# ADS8686S_BLOCK_A.net
KiCad netlist of a schematic drawn in Altium Designer
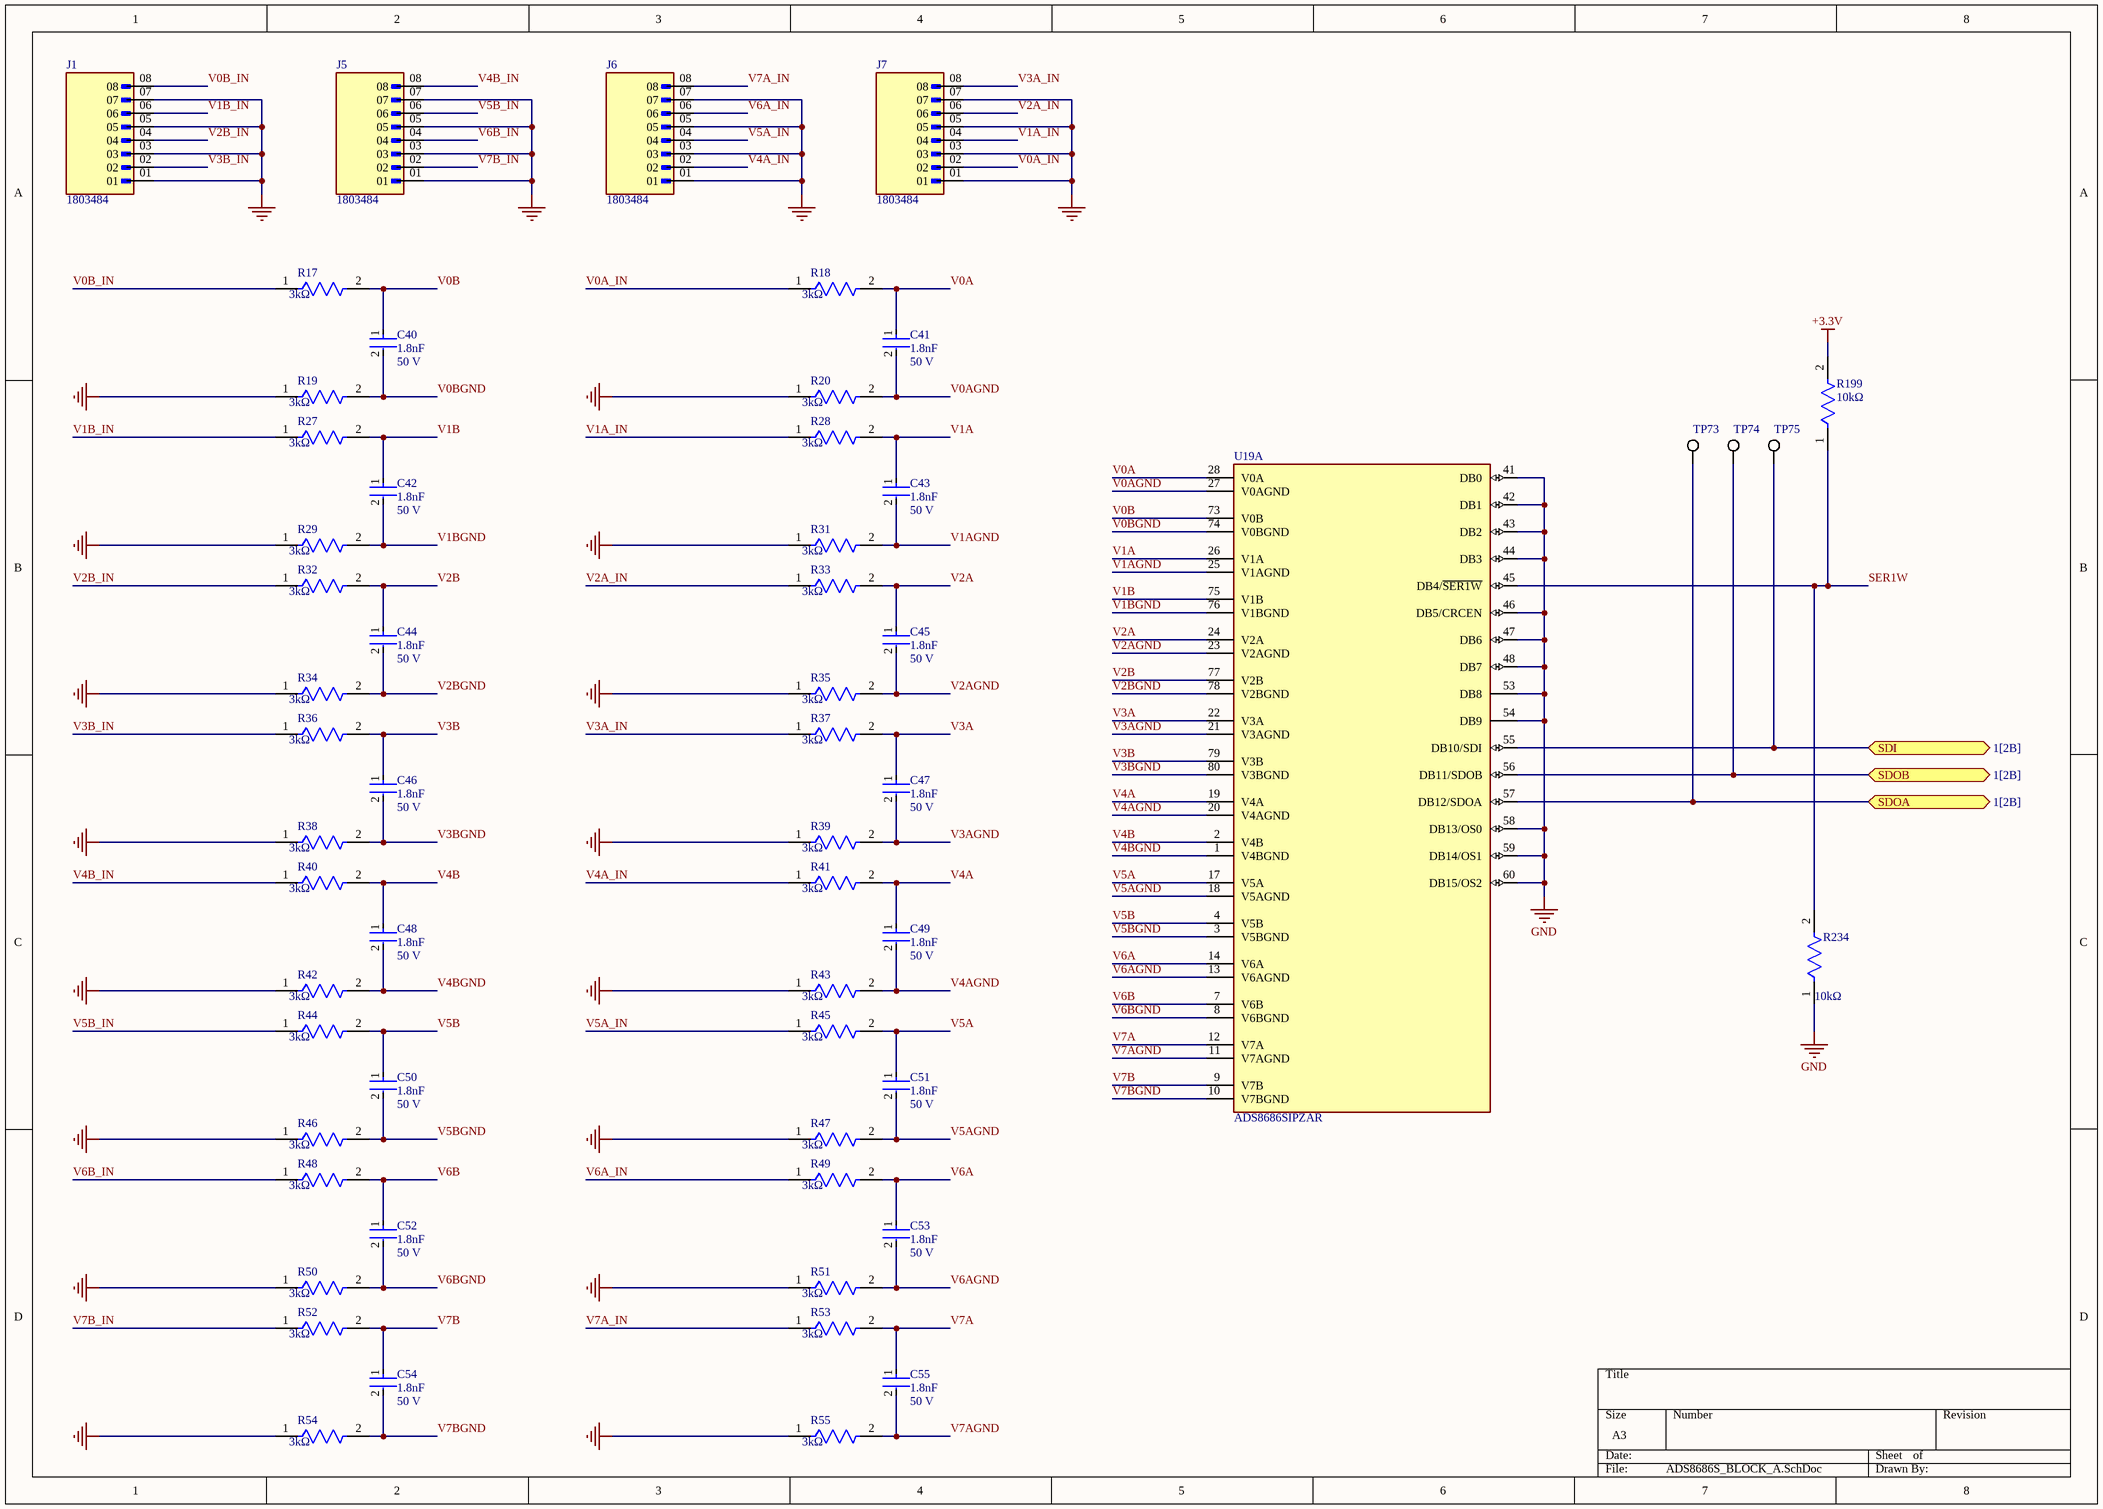
[diagram p0: ADS8686S_BLOCK_A.SchDoc]

(export (version "E")
  (design (tool "Eeschema 10.0.6"))
  (components
    (comp (ref "C40")
      (value "C0603C182J5GACTU")
      (footprint "FP-C0603C-CF-IPC_B")
      (description "CAP CER 1800PF 50V NP0 0603")
      (fields
        (field (name "OCTOPART") "https://octopart.com/c0603c182j5gactu-kemet-13174208")
        (field (name "TOLERANCE") "0.05")
        (field (name "CAPACITANCE") "1.8nF")
        (field (name "VOLTAGE RATING") "50 V")
      )
      (libsource (lib "Altium Content Vault") (part "b4654b650e69147ec39a6b967a45e02"))
    )
    (comp (ref "C41")
      (value "C0603C182J5GACTU")
      (footprint "FP-C0603C-CF-IPC_B")
      (description "CAP CER 1800PF 50V NP0 0603")
      (fields
        (field (name "OCTOPART") "https://octopart.com/c0603c182j5gactu-kemet-13174208")
        (field (name "TOLERANCE") "0.05")
        (field (name "CAPACITANCE") "1.8nF")
        (field (name "VOLTAGE RATING") "50 V")
      )
      (libsource (lib "Altium Content Vault") (part "b4654b650e69147ec39a6b967a45e02"))
    )
    (comp (ref "C42")
      (value "C0603C182J5GACTU")
      (footprint "FP-C0603C-CF-IPC_B")
      (description "CAP CER 1800PF 50V NP0 0603")
      (fields
        (field (name "OCTOPART") "https://octopart.com/c0603c182j5gactu-kemet-13174208")
        (field (name "TOLERANCE") "0.05")
        (field (name "CAPACITANCE") "1.8nF")
        (field (name "VOLTAGE RATING") "50 V")
      )
      (libsource (lib "Altium Content Vault") (part "b4654b650e69147ec39a6b967a45e02"))
    )
    (comp (ref "C43")
      (value "C0603C182J5GACTU")
      (footprint "FP-C0603C-CF-IPC_B")
      (description "CAP CER 1800PF 50V NP0 0603")
      (fields
        (field (name "OCTOPART") "https://octopart.com/c0603c182j5gactu-kemet-13174208")
        (field (name "TOLERANCE") "0.05")
        (field (name "CAPACITANCE") "1.8nF")
        (field (name "VOLTAGE RATING") "50 V")
      )
      (libsource (lib "Altium Content Vault") (part "b4654b650e69147ec39a6b967a45e02"))
    )
    (comp (ref "C44")
      (value "C0603C182J5GACTU")
      (footprint "FP-C0603C-CF-IPC_B")
      (description "CAP CER 1800PF 50V NP0 0603")
      (fields
        (field (name "OCTOPART") "https://octopart.com/c0603c182j5gactu-kemet-13174208")
        (field (name "TOLERANCE") "0.05")
        (field (name "CAPACITANCE") "1.8nF")
        (field (name "VOLTAGE RATING") "50 V")
      )
      (libsource (lib "Altium Content Vault") (part "b4654b650e69147ec39a6b967a45e02"))
    )
    (comp (ref "C45")
      (value "C0603C182J5GACTU")
      (footprint "FP-C0603C-CF-IPC_B")
      (description "CAP CER 1800PF 50V NP0 0603")
      (fields
        (field (name "OCTOPART") "https://octopart.com/c0603c182j5gactu-kemet-13174208")
        (field (name "TOLERANCE") "0.05")
        (field (name "CAPACITANCE") "1.8nF")
        (field (name "VOLTAGE RATING") "50 V")
      )
      (libsource (lib "Altium Content Vault") (part "b4654b650e69147ec39a6b967a45e02"))
    )
    (comp (ref "C46")
      (value "C0603C182J5GACTU")
      (footprint "FP-C0603C-CF-IPC_B")
      (description "CAP CER 1800PF 50V NP0 0603")
      (fields
        (field (name "OCTOPART") "https://octopart.com/c0603c182j5gactu-kemet-13174208")
        (field (name "TOLERANCE") "0.05")
        (field (name "CAPACITANCE") "1.8nF")
        (field (name "VOLTAGE RATING") "50 V")
      )
      (libsource (lib "Altium Content Vault") (part "b4654b650e69147ec39a6b967a45e02"))
    )
    (comp (ref "C47")
      (value "C0603C182J5GACTU")
      (footprint "FP-C0603C-CF-IPC_B")
      (description "CAP CER 1800PF 50V NP0 0603")
      (fields
        (field (name "OCTOPART") "https://octopart.com/c0603c182j5gactu-kemet-13174208")
        (field (name "TOLERANCE") "0.05")
        (field (name "CAPACITANCE") "1.8nF")
        (field (name "VOLTAGE RATING") "50 V")
      )
      (libsource (lib "Altium Content Vault") (part "b4654b650e69147ec39a6b967a45e02"))
    )
    (comp (ref "C48")
      (value "C0603C182J5GACTU")
      (footprint "FP-C0603C-CF-IPC_B")
      (description "CAP CER 1800PF 50V NP0 0603")
      (fields
        (field (name "OCTOPART") "https://octopart.com/c0603c182j5gactu-kemet-13174208")
        (field (name "TOLERANCE") "0.05")
        (field (name "CAPACITANCE") "1.8nF")
        (field (name "VOLTAGE RATING") "50 V")
      )
      (libsource (lib "Altium Content Vault") (part "b4654b650e69147ec39a6b967a45e02"))
    )
    (comp (ref "C49")
      (value "C0603C182J5GACTU")
      (footprint "FP-C0603C-CF-IPC_B")
      (description "CAP CER 1800PF 50V NP0 0603")
      (fields
        (field (name "OCTOPART") "https://octopart.com/c0603c182j5gactu-kemet-13174208")
        (field (name "TOLERANCE") "0.05")
        (field (name "CAPACITANCE") "1.8nF")
        (field (name "VOLTAGE RATING") "50 V")
      )
      (libsource (lib "Altium Content Vault") (part "b4654b650e69147ec39a6b967a45e02"))
    )
    (comp (ref "C50")
      (value "C0603C182J5GACTU")
      (footprint "FP-C0603C-CF-IPC_B")
      (description "CAP CER 1800PF 50V NP0 0603")
      (fields
        (field (name "OCTOPART") "https://octopart.com/c0603c182j5gactu-kemet-13174208")
        (field (name "TOLERANCE") "0.05")
        (field (name "CAPACITANCE") "1.8nF")
        (field (name "VOLTAGE RATING") "50 V")
      )
      (libsource (lib "Altium Content Vault") (part "b4654b650e69147ec39a6b967a45e02"))
    )
    (comp (ref "C51")
      (value "C0603C182J5GACTU")
      (footprint "FP-C0603C-CF-IPC_B")
      (description "CAP CER 1800PF 50V NP0 0603")
      (fields
        (field (name "OCTOPART") "https://octopart.com/c0603c182j5gactu-kemet-13174208")
        (field (name "TOLERANCE") "0.05")
        (field (name "CAPACITANCE") "1.8nF")
        (field (name "VOLTAGE RATING") "50 V")
      )
      (libsource (lib "Altium Content Vault") (part "b4654b650e69147ec39a6b967a45e02"))
    )
    (comp (ref "C52")
      (value "C0603C182J5GACTU")
      (footprint "FP-C0603C-CF-IPC_B")
      (description "CAP CER 1800PF 50V NP0 0603")
      (fields
        (field (name "OCTOPART") "https://octopart.com/c0603c182j5gactu-kemet-13174208")
        (field (name "TOLERANCE") "0.05")
        (field (name "CAPACITANCE") "1.8nF")
        (field (name "VOLTAGE RATING") "50 V")
      )
      (libsource (lib "Altium Content Vault") (part "b4654b650e69147ec39a6b967a45e02"))
    )
    (comp (ref "C53")
      (value "C0603C182J5GACTU")
      (footprint "FP-C0603C-CF-IPC_B")
      (description "CAP CER 1800PF 50V NP0 0603")
      (fields
        (field (name "OCTOPART") "https://octopart.com/c0603c182j5gactu-kemet-13174208")
        (field (name "TOLERANCE") "0.05")
        (field (name "CAPACITANCE") "1.8nF")
        (field (name "VOLTAGE RATING") "50 V")
      )
      (libsource (lib "Altium Content Vault") (part "b4654b650e69147ec39a6b967a45e02"))
    )
    (comp (ref "C54")
      (value "C0603C182J5GACTU")
      (footprint "FP-C0603C-CF-IPC_B")
      (description "CAP CER 1800PF 50V NP0 0603")
      (fields
        (field (name "OCTOPART") "https://octopart.com/c0603c182j5gactu-kemet-13174208")
        (field (name "TOLERANCE") "0.05")
        (field (name "CAPACITANCE") "1.8nF")
        (field (name "VOLTAGE RATING") "50 V")
      )
      (libsource (lib "Altium Content Vault") (part "b4654b650e69147ec39a6b967a45e02"))
    )
    (comp (ref "C55")
      (value "C0603C182J5GACTU")
      (footprint "FP-C0603C-CF-IPC_B")
      (description "CAP CER 1800PF 50V NP0 0603")
      (fields
        (field (name "OCTOPART") "https://octopart.com/c0603c182j5gactu-kemet-13174208")
        (field (name "TOLERANCE") "0.05")
        (field (name "CAPACITANCE") "1.8nF")
        (field (name "VOLTAGE RATING") "50 V")
      )
      (libsource (lib "Altium Content Vault") (part "b4654b650e69147ec39a6b967a45e02"))
    )
    (comp (ref "J1")
      (value "1803484")
      (footprint "1803484:PHOENIX_1803484")
      (fields (field (name "MF") "{'manufacturer': u'Phoenix Contact'}"))
      (libsource (lib "*") (part "1803484"))
    )
    (comp (ref "J5")
      (value "1803484")
      (footprint "1803484:PHOENIX_1803484")
      (fields (field (name "MF") "{'manufacturer': u'Phoenix Contact'}"))
      (libsource (lib "*") (part "1803484"))
    )
    (comp (ref "J6")
      (value "1803484")
      (footprint "1803484:PHOENIX_1803484")
      (fields (field (name "MF") "{'manufacturer': u'Phoenix Contact'}"))
      (libsource (lib "*") (part "1803484"))
    )
    (comp (ref "J7")
      (value "1803484")
      (footprint "1803484:PHOENIX_1803484")
      (fields (field (name "MF") "{'manufacturer': u'Phoenix Contact'}"))
      (libsource (lib "*") (part "1803484"))
    )
    (comp (ref "R17")
      (value "AC0603FR-073KL")
      (footprint "FP-AC0603-IPC_B")
      (description "RES 3kΩ 1.00% 0.1W 0603")
      (fields (field (name "TOLERANCE") "1%") (field (name "RESISTANCE") "3kΩ"))
      (libsource (lib "Altium Content Vault") (part "1029c3af85768c4190bb7ad29bc67b5"))
    )
    (comp (ref "R18")
      (value "AC0603FR-073KL")
      (footprint "FP-AC0603-IPC_B")
      (description "RES 3kΩ 1.00% 0.1W 0603")
      (fields (field (name "TOLERANCE") "1%") (field (name "RESISTANCE") "3kΩ"))
      (libsource (lib "Altium Content Vault") (part "1029c3af85768c4190bb7ad29bc67b5"))
    )
    (comp (ref "R19")
      (value "AC0603FR-073KL")
      (footprint "FP-AC0603-IPC_B")
      (description "RES 3kΩ 1.00% 0.1W 0603")
      (fields (field (name "TOLERANCE") "1%") (field (name "RESISTANCE") "3kΩ"))
      (libsource (lib "Altium Content Vault") (part "1029c3af85768c4190bb7ad29bc67b5"))
    )
    (comp (ref "R20")
      (value "AC0603FR-073KL")
      (footprint "FP-AC0603-IPC_B")
      (description "RES 3kΩ 1.00% 0.1W 0603")
      (fields (field (name "TOLERANCE") "1%") (field (name "RESISTANCE") "3kΩ"))
      (libsource (lib "Altium Content Vault") (part "1029c3af85768c4190bb7ad29bc67b5"))
    )
    (comp (ref "R27")
      (value "AC0603FR-073KL")
      (footprint "FP-AC0603-IPC_B")
      (description "RES 3kΩ 1.00% 0.1W 0603")
      (fields (field (name "TOLERANCE") "1%") (field (name "RESISTANCE") "3kΩ"))
      (libsource (lib "Altium Content Vault") (part "1029c3af85768c4190bb7ad29bc67b5"))
    )
    (comp (ref "R28")
      (value "AC0603FR-073KL")
      (footprint "FP-AC0603-IPC_B")
      (description "RES 3kΩ 1.00% 0.1W 0603")
      (fields (field (name "TOLERANCE") "1%") (field (name "RESISTANCE") "3kΩ"))
      (libsource (lib "Altium Content Vault") (part "1029c3af85768c4190bb7ad29bc67b5"))
    )
    (comp (ref "R29")
      (value "AC0603FR-073KL")
      (footprint "FP-AC0603-IPC_B")
      (description "RES 3kΩ 1.00% 0.1W 0603")
      (fields (field (name "TOLERANCE") "1%") (field (name "RESISTANCE") "3kΩ"))
      (libsource (lib "Altium Content Vault") (part "1029c3af85768c4190bb7ad29bc67b5"))
    )
    (comp (ref "R31")
      (value "AC0603FR-073KL")
      (footprint "FP-AC0603-IPC_B")
      (description "RES 3kΩ 1.00% 0.1W 0603")
      (fields (field (name "TOLERANCE") "1%") (field (name "RESISTANCE") "3kΩ"))
      (libsource (lib "Altium Content Vault") (part "1029c3af85768c4190bb7ad29bc67b5"))
    )
    (comp (ref "R32")
      (value "AC0603FR-073KL")
      (footprint "FP-AC0603-IPC_B")
      (description "RES 3kΩ 1.00% 0.1W 0603")
      (fields (field (name "TOLERANCE") "1%") (field (name "RESISTANCE") "3kΩ"))
      (libsource (lib "Altium Content Vault") (part "1029c3af85768c4190bb7ad29bc67b5"))
    )
    (comp (ref "R33")
      (value "AC0603FR-073KL")
      (footprint "FP-AC0603-IPC_B")
      (description "RES 3kΩ 1.00% 0.1W 0603")
      (fields (field (name "TOLERANCE") "1%") (field (name "RESISTANCE") "3kΩ"))
      (libsource (lib "Altium Content Vault") (part "1029c3af85768c4190bb7ad29bc67b5"))
    )
    (comp (ref "R34")
      (value "AC0603FR-073KL")
      (footprint "FP-AC0603-IPC_B")
      (description "RES 3kΩ 1.00% 0.1W 0603")
      (fields (field (name "TOLERANCE") "1%") (field (name "RESISTANCE") "3kΩ"))
      (libsource (lib "Altium Content Vault") (part "1029c3af85768c4190bb7ad29bc67b5"))
    )
    (comp (ref "R35")
      (value "AC0603FR-073KL")
      (footprint "FP-AC0603-IPC_B")
      (description "RES 3kΩ 1.00% 0.1W 0603")
      (fields (field (name "TOLERANCE") "1%") (field (name "RESISTANCE") "3kΩ"))
      (libsource (lib "Altium Content Vault") (part "1029c3af85768c4190bb7ad29bc67b5"))
    )
    (comp (ref "R36")
      (value "AC0603FR-073KL")
      (footprint "FP-AC0603-IPC_B")
      (description "RES 3kΩ 1.00% 0.1W 0603")
      (fields (field (name "TOLERANCE") "1%") (field (name "RESISTANCE") "3kΩ"))
      (libsource (lib "Altium Content Vault") (part "1029c3af85768c4190bb7ad29bc67b5"))
    )
    (comp (ref "R37")
      (value "AC0603FR-073KL")
      (footprint "FP-AC0603-IPC_B")
      (description "RES 3kΩ 1.00% 0.1W 0603")
      (fields (field (name "TOLERANCE") "1%") (field (name "RESISTANCE") "3kΩ"))
      (libsource (lib "Altium Content Vault") (part "1029c3af85768c4190bb7ad29bc67b5"))
    )
    (comp (ref "R38")
      (value "AC0603FR-073KL")
      (footprint "FP-AC0603-IPC_B")
      (description "RES 3kΩ 1.00% 0.1W 0603")
      (fields (field (name "TOLERANCE") "1%") (field (name "RESISTANCE") "3kΩ"))
      (libsource (lib "Altium Content Vault") (part "1029c3af85768c4190bb7ad29bc67b5"))
    )
    (comp (ref "R39")
      (value "AC0603FR-073KL")
      (footprint "FP-AC0603-IPC_B")
      (description "RES 3kΩ 1.00% 0.1W 0603")
      (fields (field (name "TOLERANCE") "1%") (field (name "RESISTANCE") "3kΩ"))
      (libsource (lib "Altium Content Vault") (part "1029c3af85768c4190bb7ad29bc67b5"))
    )
    (comp (ref "R40")
      (value "AC0603FR-073KL")
      (footprint "FP-AC0603-IPC_B")
      (description "RES 3kΩ 1.00% 0.1W 0603")
      (fields (field (name "TOLERANCE") "1%") (field (name "RESISTANCE") "3kΩ"))
      (libsource (lib "Altium Content Vault") (part "1029c3af85768c4190bb7ad29bc67b5"))
    )
    (comp (ref "R41")
      (value "AC0603FR-073KL")
      (footprint "FP-AC0603-IPC_B")
      (description "RES 3kΩ 1.00% 0.1W 0603")
      (fields (field (name "TOLERANCE") "1%") (field (name "RESISTANCE") "3kΩ"))
      (libsource (lib "Altium Content Vault") (part "1029c3af85768c4190bb7ad29bc67b5"))
    )
    (comp (ref "R42")
      (value "AC0603FR-073KL")
      (footprint "FP-AC0603-IPC_B")
      (description "RES 3kΩ 1.00% 0.1W 0603")
      (fields (field (name "TOLERANCE") "1%") (field (name "RESISTANCE") "3kΩ"))
      (libsource (lib "Altium Content Vault") (part "1029c3af85768c4190bb7ad29bc67b5"))
    )
    (comp (ref "R43")
      (value "AC0603FR-073KL")
      (footprint "FP-AC0603-IPC_B")
      (description "RES 3kΩ 1.00% 0.1W 0603")
      (fields (field (name "TOLERANCE") "1%") (field (name "RESISTANCE") "3kΩ"))
      (libsource (lib "Altium Content Vault") (part "1029c3af85768c4190bb7ad29bc67b5"))
    )
    (comp (ref "R44")
      (value "AC0603FR-073KL")
      (footprint "FP-AC0603-IPC_B")
      (description "RES 3kΩ 1.00% 0.1W 0603")
      (fields (field (name "TOLERANCE") "1%") (field (name "RESISTANCE") "3kΩ"))
      (libsource (lib "Altium Content Vault") (part "1029c3af85768c4190bb7ad29bc67b5"))
    )
    (comp (ref "R45")
      (value "AC0603FR-073KL")
      (footprint "FP-AC0603-IPC_B")
      (description "RES 3kΩ 1.00% 0.1W 0603")
      (fields (field (name "TOLERANCE") "1%") (field (name "RESISTANCE") "3kΩ"))
      (libsource (lib "Altium Content Vault") (part "1029c3af85768c4190bb7ad29bc67b5"))
    )
    (comp (ref "R46")
      (value "AC0603FR-073KL")
      (footprint "FP-AC0603-IPC_B")
      (description "RES 3kΩ 1.00% 0.1W 0603")
      (fields (field (name "TOLERANCE") "1%") (field (name "RESISTANCE") "3kΩ"))
      (libsource (lib "Altium Content Vault") (part "1029c3af85768c4190bb7ad29bc67b5"))
    )
    (comp (ref "R47")
      (value "AC0603FR-073KL")
      (footprint "FP-AC0603-IPC_B")
      (description "RES 3kΩ 1.00% 0.1W 0603")
      (fields (field (name "TOLERANCE") "1%") (field (name "RESISTANCE") "3kΩ"))
      (libsource (lib "Altium Content Vault") (part "1029c3af85768c4190bb7ad29bc67b5"))
    )
    (comp (ref "R48")
      (value "AC0603FR-073KL")
      (footprint "FP-AC0603-IPC_B")
      (description "RES 3kΩ 1.00% 0.1W 0603")
      (fields (field (name "TOLERANCE") "1%") (field (name "RESISTANCE") "3kΩ"))
      (libsource (lib "Altium Content Vault") (part "1029c3af85768c4190bb7ad29bc67b5"))
    )
    (comp (ref "R49")
      (value "AC0603FR-073KL")
      (footprint "FP-AC0603-IPC_B")
      (description "RES 3kΩ 1.00% 0.1W 0603")
      (fields (field (name "TOLERANCE") "1%") (field (name "RESISTANCE") "3kΩ"))
      (libsource (lib "Altium Content Vault") (part "1029c3af85768c4190bb7ad29bc67b5"))
    )
    (comp (ref "R50")
      (value "AC0603FR-073KL")
      (footprint "FP-AC0603-IPC_B")
      (description "RES 3kΩ 1.00% 0.1W 0603")
      (fields (field (name "TOLERANCE") "1%") (field (name "RESISTANCE") "3kΩ"))
      (libsource (lib "Altium Content Vault") (part "1029c3af85768c4190bb7ad29bc67b5"))
    )
    (comp (ref "R51")
      (value "AC0603FR-073KL")
      (footprint "FP-AC0603-IPC_B")
      (description "RES 3kΩ 1.00% 0.1W 0603")
      (fields (field (name "TOLERANCE") "1%") (field (name "RESISTANCE") "3kΩ"))
      (libsource (lib "Altium Content Vault") (part "1029c3af85768c4190bb7ad29bc67b5"))
    )
    (comp (ref "R52")
      (value "AC0603FR-073KL")
      (footprint "FP-AC0603-IPC_B")
      (description "RES 3kΩ 1.00% 0.1W 0603")
      (fields (field (name "TOLERANCE") "1%") (field (name "RESISTANCE") "3kΩ"))
      (libsource (lib "Altium Content Vault") (part "1029c3af85768c4190bb7ad29bc67b5"))
    )
    (comp (ref "R53")
      (value "AC0603FR-073KL")
      (footprint "FP-AC0603-IPC_B")
      (description "RES 3kΩ 1.00% 0.1W 0603")
      (fields (field (name "TOLERANCE") "1%") (field (name "RESISTANCE") "3kΩ"))
      (libsource (lib "Altium Content Vault") (part "1029c3af85768c4190bb7ad29bc67b5"))
    )
    (comp (ref "R54")
      (value "AC0603FR-073KL")
      (footprint "FP-AC0603-IPC_B")
      (description "RES 3kΩ 1.00% 0.1W 0603")
      (fields (field (name "TOLERANCE") "1%") (field (name "RESISTANCE") "3kΩ"))
      (libsource (lib "Altium Content Vault") (part "1029c3af85768c4190bb7ad29bc67b5"))
    )
    (comp (ref "R55")
      (value "AC0603FR-073KL")
      (footprint "FP-AC0603-IPC_B")
      (description "RES 3kΩ 1.00% 0.1W 0603")
      (fields (field (name "TOLERANCE") "1%") (field (name "RESISTANCE") "3kΩ"))
      (libsource (lib "Altium Content Vault") (part "1029c3af85768c4190bb7ad29bc67b5"))
    )
    (comp (ref "R199")
      (value "RC0603FR-0710KL")
      (footprint "FP-RC0603-0_55-IPC_B")
      (description "RES 10K OHM 1% 1/10W 0603")
      (fields (field (name "TOLERANCE") "1%") (field (name "RESISTANCE") "10kΩ"))
      (libsource (lib "Altium Content Vault") (part "1029c3af85768c4190bb7ad29bc67b5"))
    )
    (comp (ref "R234")
      (value "RC0603FR-0710KL")
      (footprint "FP-RC0603-0_55-IPC_B")
      (description "RES 10K OHM 1% 1/10W 0603")
      (fields (field (name "TOLERANCE") "1%") (field (name "RESISTANCE") "10kΩ"))
      (libsource (lib "Altium Content Vault") (part "1029c3af85768c4190bb7ad29bc67b5"))
    )
    (comp (ref "TP73")
      (value "5019")
      (footprint "KSTN-5019_V")
      (description "Test Point, 1 Position SMD, RoHS, Tape and Reel")
      (libsource (lib "Altium Content Vault") (part "TESTPOINT_WHITE"))
    )
    (comp (ref "TP74")
      (value "5019")
      (footprint "KSTN-5019_V")
      (description "Test Point, 1 Position SMD, RoHS, Tape and Reel")
      (libsource (lib "Altium Content Vault") (part "TESTPOINT_WHITE"))
    )
    (comp (ref "TP75")
      (value "5019")
      (footprint "KSTN-5019_V")
      (description "Test Point, 1 Position SMD, RoHS, Tape and Reel")
      (libsource (lib "Altium Content Vault") (part "TESTPOINT_WHITE"))
    )
    (comp (ref "U19")
      (value "ADS8686SIPZAR")
      (footprint "TI-RECOMMENDED")
      (fields (field (name "MANUFACTURER") "Texas Instruments"))
      (libsource (lib "ADS8686S") (part "ADS8686SIPZAR"))
    )
  )
  (nets
    (net (code "1") (name "+3.3V") (class "Default")
      (node (ref "R199") (pin "2") (pinfunction "2_2") (pintype "passive"))
    )
    (net (code "2") (name "/SDI") (class "Default")
      (node (ref "TP75") (pin "1") (pinfunction "1_1") (pintype "passive"))
      (node (ref "U19") (pin "55") (pinfunction "DB10/SDI_55") (pintype "bidirectional"))
    )
    (net (code "3") (name "/SDOA") (class "Default")
      (node (ref "TP73") (pin "1") (pinfunction "1_1") (pintype "passive"))
      (node (ref "U19") (pin "57") (pinfunction "DB12/SDOA_57") (pintype "bidirectional"))
    )
    (net (code "4") (name "/SDOB") (class "Default")
      (node (ref "TP74") (pin "1") (pinfunction "1_1") (pintype "passive"))
      (node (ref "U19") (pin "56") (pinfunction "DB11/SDOB_56") (pintype "bidirectional"))
    )
    (net (code "5") (name "/SER1W") (class "Default")
      (node (ref "R199") (pin "1") (pinfunction "1_1") (pintype "passive"))
      (node (ref "R234") (pin "2") (pinfunction "2_2") (pintype "passive"))
      (node (ref "U19") (pin "45") (pinfunction "DB4/~{SER1W}_45") (pintype "bidirectional"))
    )
    (net (code "6") (name "/V0A") (class "Default")
      (node (ref "C41") (pin "1") (pinfunction "1_1") (pintype "passive"))
      (node (ref "R18") (pin "2") (pinfunction "2_2") (pintype "passive"))
      (node (ref "U19") (pin "28") (pinfunction "V0A_28") (pintype "power_in"))
    )
    (net (code "7") (name "/V0AGND") (class "Default")
      (node (ref "C41") (pin "2") (pinfunction "2_2") (pintype "passive"))
      (node (ref "R20") (pin "2") (pinfunction "2_2") (pintype "passive"))
      (node (ref "U19") (pin "27") (pinfunction "V0AGND_27") (pintype "power_in"))
    )
    (net (code "8") (name "/V0A_IN") (class "Default")
      (node (ref "J7") (pin "02") (pinfunction "02_02") (pintype "passive"))
      (node (ref "R18") (pin "1") (pinfunction "1_1") (pintype "passive"))
    )
    (net (code "9") (name "/V0B") (class "Default")
      (node (ref "C40") (pin "1") (pinfunction "1_1") (pintype "passive"))
      (node (ref "R17") (pin "2") (pinfunction "2_2") (pintype "passive"))
      (node (ref "U19") (pin "73") (pinfunction "V0B_73") (pintype "power_in"))
    )
    (net (code "10") (name "/V0BGND") (class "Default")
      (node (ref "C40") (pin "2") (pinfunction "2_2") (pintype "passive"))
      (node (ref "R19") (pin "2") (pinfunction "2_2") (pintype "passive"))
      (node (ref "U19") (pin "74") (pinfunction "V0BGND_74") (pintype "power_in"))
    )
    (net (code "11") (name "/V0B_IN") (class "Default")
      (node (ref "J1") (pin "08") (pinfunction "08_08") (pintype "passive"))
      (node (ref "R17") (pin "1") (pinfunction "1_1") (pintype "passive"))
    )
    (net (code "12") (name "/V1A") (class "Default")
      (node (ref "C43") (pin "1") (pinfunction "1_1") (pintype "passive"))
      (node (ref "R28") (pin "2") (pinfunction "2_2") (pintype "passive"))
      (node (ref "U19") (pin "26") (pinfunction "V1A_26") (pintype "power_in"))
    )
    (net (code "13") (name "/V1AGND") (class "Default")
      (node (ref "C43") (pin "2") (pinfunction "2_2") (pintype "passive"))
      (node (ref "R31") (pin "2") (pinfunction "2_2") (pintype "passive"))
      (node (ref "U19") (pin "25") (pinfunction "V1AGND_25") (pintype "power_in"))
    )
    (net (code "14") (name "/V1A_IN") (class "Default")
      (node (ref "J7") (pin "04") (pinfunction "04_04") (pintype "passive"))
      (node (ref "R28") (pin "1") (pinfunction "1_1") (pintype "passive"))
    )
    (net (code "15") (name "/V1B") (class "Default")
      (node (ref "C42") (pin "1") (pinfunction "1_1") (pintype "passive"))
      (node (ref "R27") (pin "2") (pinfunction "2_2") (pintype "passive"))
      (node (ref "U19") (pin "75") (pinfunction "V1B_75") (pintype "power_in"))
    )
    (net (code "16") (name "/V1BGND") (class "Default")
      (node (ref "C42") (pin "2") (pinfunction "2_2") (pintype "passive"))
      (node (ref "R29") (pin "2") (pinfunction "2_2") (pintype "passive"))
      (node (ref "U19") (pin "76") (pinfunction "V1BGND_76") (pintype "power_in"))
    )
    (net (code "17") (name "/V1B_IN") (class "Default")
      (node (ref "J1") (pin "06") (pinfunction "06_06") (pintype "passive"))
      (node (ref "R27") (pin "1") (pinfunction "1_1") (pintype "passive"))
    )
    (net (code "18") (name "/V2A") (class "Default")
      (node (ref "C45") (pin "1") (pinfunction "1_1") (pintype "passive"))
      (node (ref "R33") (pin "2") (pinfunction "2_2") (pintype "passive"))
      (node (ref "U19") (pin "24") (pinfunction "V2A_24") (pintype "power_in"))
    )
    (net (code "19") (name "/V2AGND") (class "Default")
      (node (ref "C45") (pin "2") (pinfunction "2_2") (pintype "passive"))
      (node (ref "R35") (pin "2") (pinfunction "2_2") (pintype "passive"))
      (node (ref "U19") (pin "23") (pinfunction "V2AGND_23") (pintype "power_in"))
    )
    (net (code "20") (name "/V2A_IN") (class "Default")
      (node (ref "J7") (pin "06") (pinfunction "06_06") (pintype "passive"))
      (node (ref "R33") (pin "1") (pinfunction "1_1") (pintype "passive"))
    )
    (net (code "21") (name "/V2B") (class "Default")
      (node (ref "C44") (pin "1") (pinfunction "1_1") (pintype "passive"))
      (node (ref "R32") (pin "2") (pinfunction "2_2") (pintype "passive"))
      (node (ref "U19") (pin "77") (pinfunction "V2B_77") (pintype "power_in"))
    )
    (net (code "22") (name "/V2BGND") (class "Default")
      (node (ref "C44") (pin "2") (pinfunction "2_2") (pintype "passive"))
      (node (ref "R34") (pin "2") (pinfunction "2_2") (pintype "passive"))
      (node (ref "U19") (pin "78") (pinfunction "V2BGND_78") (pintype "power_in"))
    )
    (net (code "23") (name "/V2B_IN") (class "Default")
      (node (ref "J1") (pin "04") (pinfunction "04_04") (pintype "passive"))
      (node (ref "R32") (pin "1") (pinfunction "1_1") (pintype "passive"))
    )
    (net (code "24") (name "/V3A") (class "Default")
      (node (ref "C47") (pin "1") (pinfunction "1_1") (pintype "passive"))
      (node (ref "R37") (pin "2") (pinfunction "2_2") (pintype "passive"))
      (node (ref "U19") (pin "22") (pinfunction "V3A_22") (pintype "power_in"))
    )
    (net (code "25") (name "/V3AGND") (class "Default")
      (node (ref "C47") (pin "2") (pinfunction "2_2") (pintype "passive"))
      (node (ref "R39") (pin "2") (pinfunction "2_2") (pintype "passive"))
      (node (ref "U19") (pin "21") (pinfunction "V3AGND_21") (pintype "power_in"))
    )
    (net (code "26") (name "/V3A_IN") (class "Default")
      (node (ref "J7") (pin "08") (pinfunction "08_08") (pintype "passive"))
      (node (ref "R37") (pin "1") (pinfunction "1_1") (pintype "passive"))
    )
    (net (code "27") (name "/V3B") (class "Default")
      (node (ref "C46") (pin "1") (pinfunction "1_1") (pintype "passive"))
      (node (ref "R36") (pin "2") (pinfunction "2_2") (pintype "passive"))
      (node (ref "U19") (pin "79") (pinfunction "V3B_79") (pintype "power_in"))
    )
    (net (code "28") (name "/V3BGND") (class "Default")
      (node (ref "C46") (pin "2") (pinfunction "2_2") (pintype "passive"))
      (node (ref "R38") (pin "2") (pinfunction "2_2") (pintype "passive"))
      (node (ref "U19") (pin "80") (pinfunction "V3BGND_80") (pintype "power_in"))
    )
    (net (code "29") (name "/V3B_IN") (class "Default")
      (node (ref "J1") (pin "02") (pinfunction "02_02") (pintype "passive"))
      (node (ref "R36") (pin "1") (pinfunction "1_1") (pintype "passive"))
    )
    (net (code "30") (name "/V4A") (class "Default")
      (node (ref "C49") (pin "1") (pinfunction "1_1") (pintype "passive"))
      (node (ref "R41") (pin "2") (pinfunction "2_2") (pintype "passive"))
      (node (ref "U19") (pin "19") (pinfunction "V4A_19") (pintype "power_in"))
    )
    (net (code "31") (name "/V4AGND") (class "Default")
      (node (ref "C49") (pin "2") (pinfunction "2_2") (pintype "passive"))
      (node (ref "R43") (pin "2") (pinfunction "2_2") (pintype "passive"))
      (node (ref "U19") (pin "20") (pinfunction "V4AGND_20") (pintype "power_in"))
    )
    (net (code "32") (name "/V4A_IN") (class "Default")
      (node (ref "J6") (pin "02") (pinfunction "02_02") (pintype "passive"))
      (node (ref "R41") (pin "1") (pinfunction "1_1") (pintype "passive"))
    )
    (net (code "33") (name "/V4B") (class "Default")
      (node (ref "C48") (pin "1") (pinfunction "1_1") (pintype "passive"))
      (node (ref "R40") (pin "2") (pinfunction "2_2") (pintype "passive"))
      (node (ref "U19") (pin "2") (pinfunction "V4B_2") (pintype "power_in"))
    )
    (net (code "34") (name "/V4BGND") (class "Default")
      (node (ref "C48") (pin "2") (pinfunction "2_2") (pintype "passive"))
      (node (ref "R42") (pin "2") (pinfunction "2_2") (pintype "passive"))
      (node (ref "U19") (pin "1") (pinfunction "V4BGND_1") (pintype "power_in"))
    )
    (net (code "35") (name "/V4B_IN") (class "Default")
      (node (ref "J5") (pin "08") (pinfunction "08_08") (pintype "passive"))
      (node (ref "R40") (pin "1") (pinfunction "1_1") (pintype "passive"))
    )
    (net (code "36") (name "/V5A") (class "Default")
      (node (ref "C51") (pin "1") (pinfunction "1_1") (pintype "passive"))
      (node (ref "R45") (pin "2") (pinfunction "2_2") (pintype "passive"))
      (node (ref "U19") (pin "17") (pinfunction "V5A_17") (pintype "power_in"))
    )
    (net (code "37") (name "/V5AGND") (class "Default")
      (node (ref "C51") (pin "2") (pinfunction "2_2") (pintype "passive"))
      (node (ref "R47") (pin "2") (pinfunction "2_2") (pintype "passive"))
      (node (ref "U19") (pin "18") (pinfunction "V5AGND_18") (pintype "power_in"))
    )
    (net (code "38") (name "/V5A_IN") (class "Default")
      (node (ref "J6") (pin "04") (pinfunction "04_04") (pintype "passive"))
      (node (ref "R45") (pin "1") (pinfunction "1_1") (pintype "passive"))
    )
    (net (code "39") (name "/V5B") (class "Default")
      (node (ref "C50") (pin "1") (pinfunction "1_1") (pintype "passive"))
      (node (ref "R44") (pin "2") (pinfunction "2_2") (pintype "passive"))
      (node (ref "U19") (pin "4") (pinfunction "V5B_4") (pintype "power_in"))
    )
    (net (code "40") (name "/V5BGND") (class "Default")
      (node (ref "C50") (pin "2") (pinfunction "2_2") (pintype "passive"))
      (node (ref "R46") (pin "2") (pinfunction "2_2") (pintype "passive"))
      (node (ref "U19") (pin "3") (pinfunction "V5BGND_3") (pintype "power_in"))
    )
    (net (code "41") (name "/V5B_IN") (class "Default")
      (node (ref "J5") (pin "06") (pinfunction "06_06") (pintype "passive"))
      (node (ref "R44") (pin "1") (pinfunction "1_1") (pintype "passive"))
    )
    (net (code "42") (name "/V6A") (class "Default")
      (node (ref "C53") (pin "1") (pinfunction "1_1") (pintype "passive"))
      (node (ref "R49") (pin "2") (pinfunction "2_2") (pintype "passive"))
      (node (ref "U19") (pin "14") (pinfunction "V6A_14") (pintype "power_in"))
    )
    (net (code "43") (name "/V6AGND") (class "Default")
      (node (ref "C53") (pin "2") (pinfunction "2_2") (pintype "passive"))
      (node (ref "R51") (pin "2") (pinfunction "2_2") (pintype "passive"))
      (node (ref "U19") (pin "13") (pinfunction "V6AGND_13") (pintype "power_in"))
    )
    (net (code "44") (name "/V6A_IN") (class "Default")
      (node (ref "J6") (pin "06") (pinfunction "06_06") (pintype "passive"))
      (node (ref "R49") (pin "1") (pinfunction "1_1") (pintype "passive"))
    )
    (net (code "45") (name "/V6B") (class "Default")
      (node (ref "C52") (pin "1") (pinfunction "1_1") (pintype "passive"))
      (node (ref "R48") (pin "2") (pinfunction "2_2") (pintype "passive"))
      (node (ref "U19") (pin "7") (pinfunction "V6B_7") (pintype "power_in"))
    )
    (net (code "46") (name "/V6BGND") (class "Default")
      (node (ref "C52") (pin "2") (pinfunction "2_2") (pintype "passive"))
      (node (ref "R50") (pin "2") (pinfunction "2_2") (pintype "passive"))
      (node (ref "U19") (pin "8") (pinfunction "V6BGND_8") (pintype "power_in"))
    )
    (net (code "47") (name "/V6B_IN") (class "Default")
      (node (ref "J5") (pin "04") (pinfunction "04_04") (pintype "passive"))
      (node (ref "R48") (pin "1") (pinfunction "1_1") (pintype "passive"))
    )
    (net (code "48") (name "/V7A") (class "Default")
      (node (ref "C55") (pin "1") (pinfunction "1_1") (pintype "passive"))
      (node (ref "R53") (pin "2") (pinfunction "2_2") (pintype "passive"))
      (node (ref "U19") (pin "12") (pinfunction "V7A_12") (pintype "power_in"))
    )
    (net (code "49") (name "/V7AGND") (class "Default")
      (node (ref "C55") (pin "2") (pinfunction "2_2") (pintype "passive"))
      (node (ref "R55") (pin "2") (pinfunction "2_2") (pintype "passive"))
      (node (ref "U19") (pin "11") (pinfunction "V7AGND_11") (pintype "power_in"))
    )
    (net (code "50") (name "/V7A_IN") (class "Default")
      (node (ref "J6") (pin "08") (pinfunction "08_08") (pintype "passive"))
      (node (ref "R53") (pin "1") (pinfunction "1_1") (pintype "passive"))
    )
    (net (code "51") (name "/V7B") (class "Default")
      (node (ref "C54") (pin "1") (pinfunction "1_1") (pintype "passive"))
      (node (ref "R52") (pin "2") (pinfunction "2_2") (pintype "passive"))
      (node (ref "U19") (pin "9") (pinfunction "V7B_9") (pintype "power_in"))
    )
    (net (code "52") (name "/V7BGND") (class "Default")
      (node (ref "C54") (pin "2") (pinfunction "2_2") (pintype "passive"))
      (node (ref "R54") (pin "2") (pinfunction "2_2") (pintype "passive"))
      (node (ref "U19") (pin "10") (pinfunction "V7BGND_10") (pintype "power_in"))
    )
    (net (code "53") (name "/V7B_IN") (class "Default")
      (node (ref "J5") (pin "02") (pinfunction "02_02") (pintype "passive"))
      (node (ref "R52") (pin "1") (pinfunction "1_1") (pintype "passive"))
    )
    (net (code "54") (name "GND") (class "Default")
      (node (ref "J1") (pin "01") (pinfunction "01_01") (pintype "passive"))
      (node (ref "J1") (pin "03") (pinfunction "03_03") (pintype "passive"))
      (node (ref "J1") (pin "05") (pinfunction "05_05") (pintype "passive"))
      (node (ref "J1") (pin "07") (pinfunction "07_07") (pintype "passive"))
      (node (ref "J5") (pin "01") (pinfunction "01_01") (pintype "passive"))
      (node (ref "J5") (pin "03") (pinfunction "03_03") (pintype "passive"))
      (node (ref "J5") (pin "05") (pinfunction "05_05") (pintype "passive"))
      (node (ref "J5") (pin "07") (pinfunction "07_07") (pintype "passive"))
      (node (ref "J6") (pin "01") (pinfunction "01_01") (pintype "passive"))
      (node (ref "J6") (pin "03") (pinfunction "03_03") (pintype "passive"))
      (node (ref "J6") (pin "05") (pinfunction "05_05") (pintype "passive"))
      (node (ref "J6") (pin "07") (pinfunction "07_07") (pintype "passive"))
      (node (ref "J7") (pin "01") (pinfunction "01_01") (pintype "passive"))
      (node (ref "J7") (pin "03") (pinfunction "03_03") (pintype "passive"))
      (node (ref "J7") (pin "05") (pinfunction "05_05") (pintype "passive"))
      (node (ref "J7") (pin "07") (pinfunction "07_07") (pintype "passive"))
      (node (ref "R19") (pin "1") (pinfunction "1_1") (pintype "passive"))
      (node (ref "R20") (pin "1") (pinfunction "1_1") (pintype "passive"))
      (node (ref "R234") (pin "1") (pinfunction "1_1") (pintype "passive"))
      (node (ref "R29") (pin "1") (pinfunction "1_1") (pintype "passive"))
      (node (ref "R31") (pin "1") (pinfunction "1_1") (pintype "passive"))
      (node (ref "R34") (pin "1") (pinfunction "1_1") (pintype "passive"))
      (node (ref "R35") (pin "1") (pinfunction "1_1") (pintype "passive"))
      (node (ref "R38") (pin "1") (pinfunction "1_1") (pintype "passive"))
      (node (ref "R39") (pin "1") (pinfunction "1_1") (pintype "passive"))
      (node (ref "R42") (pin "1") (pinfunction "1_1") (pintype "passive"))
      (node (ref "R43") (pin "1") (pinfunction "1_1") (pintype "passive"))
      (node (ref "R46") (pin "1") (pinfunction "1_1") (pintype "passive"))
      (node (ref "R47") (pin "1") (pinfunction "1_1") (pintype "passive"))
      (node (ref "R50") (pin "1") (pinfunction "1_1") (pintype "passive"))
      (node (ref "R51") (pin "1") (pinfunction "1_1") (pintype "passive"))
      (node (ref "R54") (pin "1") (pinfunction "1_1") (pintype "passive"))
      (node (ref "R55") (pin "1") (pinfunction "1_1") (pintype "passive"))
      (node (ref "U19") (pin "41") (pinfunction "DB0_41") (pintype "bidirectional"))
      (node (ref "U19") (pin "42") (pinfunction "DB1_42") (pintype "bidirectional"))
      (node (ref "U19") (pin "43") (pinfunction "DB2_43") (pintype "bidirectional"))
      (node (ref "U19") (pin "44") (pinfunction "DB3_44") (pintype "bidirectional"))
      (node (ref "U19") (pin "46") (pinfunction "DB5/CRCEN_46") (pintype "bidirectional"))
      (node (ref "U19") (pin "47") (pinfunction "DB6_47") (pintype "bidirectional"))
      (node (ref "U19") (pin "48") (pinfunction "DB7_48") (pintype "bidirectional"))
      (node (ref "U19") (pin "53") (pinfunction "DB8_53") (pintype "power_in"))
      (node (ref "U19") (pin "54") (pinfunction "DB9_54") (pintype "power_in"))
      (node (ref "U19") (pin "58") (pinfunction "DB13/OS0_58") (pintype "bidirectional"))
      (node (ref "U19") (pin "59") (pinfunction "DB14/OS1_59") (pintype "bidirectional"))
      (node (ref "U19") (pin "60") (pinfunction "DB15/OS2_60") (pintype "bidirectional"))
    )
  )
)
